# Proiect_TSC_v43.net
KiCad netlist of a schematic drawn in EAGLE
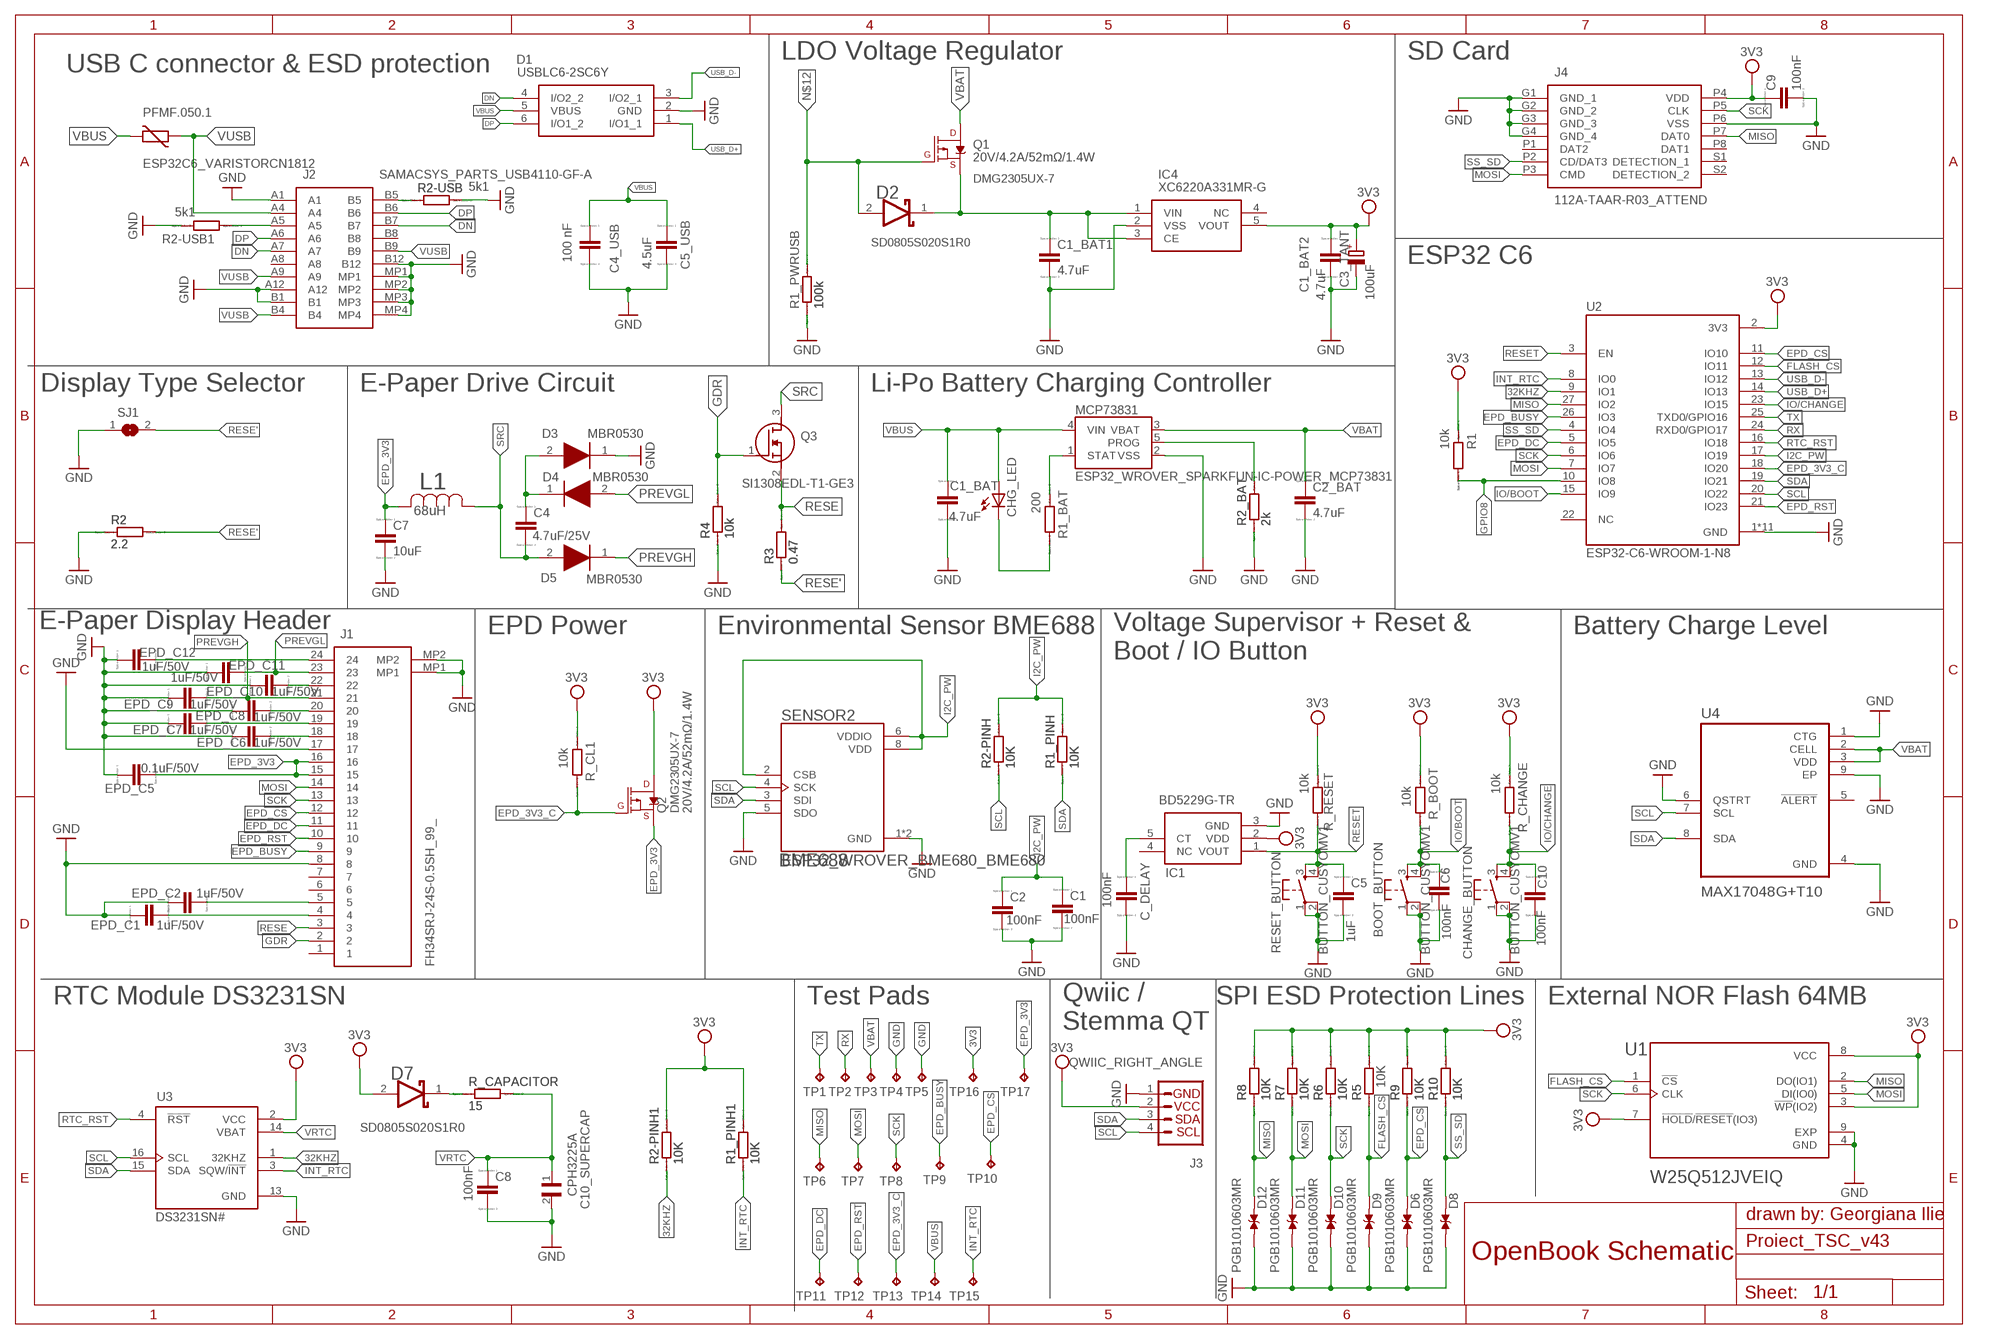
[diagram p0: schematic, sheet 1]

(export (version "E")
  (design (tool "Eeschema 10.0.6"))
  (components
    (comp (ref "BOOT_BUTTON")
      (value "BUTTON_CUSYOMV1")
      (footprint "eagle-import:MYBUTTON")
      (libsource (lib "eagle-import") (part "BUTTON_CUSYOMV1"))
    )
    (comp (ref "C1")
      (value "100nF")
      (footprint "eagle-import:EAGLE-LTSPICE_C0402")
      (libsource (lib "eagle-import") (part "EAGLE-LTSPICE_CC0402"))
    )
    (comp (ref "C1_BAT")
      (value "4.7uF")
      (footprint "eagle-import:EAGLE-LTSPICE_C0402")
      (libsource (lib "eagle-import") (part "EAGLE-LTSPICE_CC0402"))
    )
    (comp (ref "C1_BAT1")
      (value "4.7uF")
      (footprint "eagle-import:ESP32_WROVER_EAGLE-LTSPICE_C0402")
      (libsource (lib "eagle-import") (part "ESP32_WROVER_EAGLE-LTSPICE_CC0402"))
    )
    (comp (ref "C1_BAT2")
      (value "4.7uF")
      (footprint "eagle-import:ESP32_WROVER_EAGLE-LTSPICE_C0402")
      (libsource (lib "eagle-import") (part "ESP32_WROVER_EAGLE-LTSPICE_CC0402"))
    )
    (comp (ref "C2")
      (value "100nF")
      (footprint "eagle-import:EAGLE-LTSPICE_C0402")
      (libsource (lib "eagle-import") (part "EAGLE-LTSPICE_CC0402"))
    )
    (comp (ref "C2_BAT")
      (value "4.7uF")
      (footprint "eagle-import:EAGLE-LTSPICE_C0402")
      (libsource (lib "eagle-import") (part "EAGLE-LTSPICE_CC0402"))
    )
    (comp (ref "C3_TANT")
      (value "100uF")
      (footprint "eagle-import:RCL_CT3528")
      (libsource (lib "eagle-import") (part "RCL_CPOL-EUCT3528"))
    )
    (comp (ref "C4")
      (value "4.7uF/25V")
      (footprint "eagle-import:EAGLE-LTSPICE_C0402")
      (libsource (lib "eagle-import") (part "EAGLE-LTSPICE_CC0402"))
    )
    (comp (ref "C4_USB")
      (value "100 nF")
      (footprint "eagle-import:ESP32_WROVER_EAGLE-LTSPICE_C0402")
      (libsource (lib "eagle-import") (part "ESP32_WROVER_EAGLE-LTSPICE_CC0402"))
    )
    (comp (ref "C5")
      (value "1uF")
      (footprint "eagle-import:EAGLE-LTSPICE_C0402")
      (libsource (lib "eagle-import") (part "EAGLE-LTSPICE_CC0402"))
    )
    (comp (ref "C5_USB")
      (value "4.5uF")
      (footprint "eagle-import:ESP32_WROVER_EAGLE-LTSPICE_C0402")
      (libsource (lib "eagle-import") (part "ESP32_WROVER_EAGLE-LTSPICE_CC0402"))
    )
    (comp (ref "C6")
      (value "100nF")
      (footprint "eagle-import:EAGLE-LTSPICE_C0402")
      (libsource (lib "eagle-import") (part "EAGLE-LTSPICE_CC0402"))
    )
    (comp (ref "C7")
      (value "10uF")
      (footprint "eagle-import:EAGLE-LTSPICE_C0402")
      (libsource (lib "eagle-import") (part "EAGLE-LTSPICE_CC0402"))
    )
    (comp (ref "C8")
      (value "100nF")
      (footprint "eagle-import:EAGLE-LTSPICE_C0402")
      (libsource (lib "eagle-import") (part "EAGLE-LTSPICE_CC0402"))
    )
    (comp (ref "C9")
      (value "100nF")
      (footprint "eagle-import:EAGLE-LTSPICE_C0402")
      (libsource (lib "eagle-import") (part "EAGLE-LTSPICE_CC0402"))
    )
    (comp (ref "C10")
      (value "100nF")
      (footprint "eagle-import:EAGLE-LTSPICE_C0402")
      (libsource (lib "eagle-import") (part "EAGLE-LTSPICE_CC0402"))
    )
    (comp (ref "C10_SUPERCAP")
      (value "CPH3225A")
      (footprint "eagle-import:CAPCP3225X100N")
      (fields (field (name "MF") "Seiko Instruments"))
      (libsource (lib "eagle-import") (part "CPH3225A"))
    )
    (comp (ref "CHANGE_BUTTON")
      (value "BUTTON_CUSYOMV1")
      (footprint "eagle-import:MYBUTTON")
      (libsource (lib "eagle-import") (part "BUTTON_CUSYOMV1"))
    )
    (comp (ref "CHG_LED")
      (value "ADAFRUIT_LEDCHIP-LED0603")
      (footprint "eagle-import:ADAFRUIT_CHIP-LED0603")
      (libsource (lib "eagle-import") (part "ADAFRUIT_LEDCHIP-LED0603"))
    )
    (comp (ref "C_DELAY")
      (value "100nF")
      (footprint "eagle-import:EAGLE-LTSPICE_C0402")
      (libsource (lib "eagle-import") (part "EAGLE-LTSPICE_CC0402"))
    )
    (comp (ref "D1")
      (value "USBLC6-2SC6Y")
      (footprint "eagle-import:SOT95P280X145-6N")
      (fields (field (name "MF") "STMicroelectronics"))
      (libsource (lib "eagle-import") (part "USBLC6-2SC6Y"))
    )
    (comp (ref "D2")
      (value "ESP32_WROVER_AVX---SD0805S020S1R0_AVX_SD0805S020S1R0_0_0AVX_SD0805S020S1R0_0_0")
      (footprint "eagle-import:ESP32_WROVER_AVX---SD0805S020S1R0_AVX_SD0805S020S1R0_0")
      (fields
        (field (name "DIGIKEY_PART_NUMBER") "478-7800-1-ND")
        (field (name "MF") "AVX")
        (field (name "MOUSER_PART_NUMBER") "581-SD0805S020S1R0")
      )
      (libsource (lib "eagle-import") (part "ESP32_WROVER_AVX---SD0805S020S1R0_AVX_SD0805S020S1R0_0_0AVX_SD0805S020S1R0_0_0"))
    )
    (comp (ref "D3")
      (value "MBR0530")
      (footprint "eagle-import:SOD3716X135N")
      (fields (field (name "MF") "ON Semiconductor"))
      (libsource (lib "eagle-import") (part "MBR0530"))
    )
    (comp (ref "D4")
      (value "MBR0530")
      (footprint "eagle-import:SOD3716X135N")
      (fields (field (name "MF") "ON Semiconductor"))
      (libsource (lib "eagle-import") (part "MBR0530"))
    )
    (comp (ref "D5")
      (value "MBR0530")
      (footprint "eagle-import:SOD3716X135N")
      (fields (field (name "MF") "ON Semiconductor"))
      (libsource (lib "eagle-import") (part "MBR0530"))
    )
    (comp (ref "D6")
      (value "PGB1010603MR")
      (footprint "eagle-import:DIOC1608X36N")
      (fields (field (name "MF") "Littelfuse Inc."))
      (libsource (lib "eagle-import") (part "PGB1010603MR"))
    )
    (comp (ref "D7")
      (value "ESP32_WROVER_AVX---SD0805S020S1R0_AVX_SD0805S020S1R0_0_0AVX_SD0805S020S1R0_0_0")
      (footprint "eagle-import:ESP32_WROVER_AVX---SD0805S020S1R0_AVX_SD0805S020S1R0_0")
      (fields
        (field (name "DIGIKEY_PART_NUMBER") "478-7800-1-ND")
        (field (name "MF") "AVX")
        (field (name "MOUSER_PART_NUMBER") "581-SD0805S020S1R0")
      )
      (libsource (lib "eagle-import") (part "ESP32_WROVER_AVX---SD0805S020S1R0_AVX_SD0805S020S1R0_0_0AVX_SD0805S020S1R0_0_0"))
    )
    (comp (ref "D8")
      (value "PGB1010603MR")
      (footprint "eagle-import:DIOC1608X36N")
      (fields (field (name "MF") "Littelfuse Inc."))
      (libsource (lib "eagle-import") (part "PGB1010603MR"))
    )
    (comp (ref "D9")
      (value "PGB1010603MR")
      (footprint "eagle-import:DIOC1608X36N")
      (fields (field (name "MF") "Littelfuse Inc."))
      (libsource (lib "eagle-import") (part "PGB1010603MR"))
    )
    (comp (ref "D10")
      (value "PGB1010603MR")
      (footprint "eagle-import:DIOC1608X36N")
      (fields (field (name "MF") "Littelfuse Inc."))
      (libsource (lib "eagle-import") (part "PGB1010603MR"))
    )
    (comp (ref "D11")
      (value "PGB1010603MR")
      (footprint "eagle-import:DIOC1608X36N")
      (fields (field (name "MF") "Littelfuse Inc."))
      (libsource (lib "eagle-import") (part "PGB1010603MR"))
    )
    (comp (ref "D12")
      (value "PGB1010603MR")
      (footprint "eagle-import:DIOC1608X36N")
      (fields (field (name "MF") "Littelfuse Inc."))
      (libsource (lib "eagle-import") (part "PGB1010603MR"))
    )
    (comp (ref "EPD_C1")
      (value "1uF/50V")
      (footprint "eagle-import:EAGLE-LTSPICE_C0402")
      (libsource (lib "eagle-import") (part "EAGLE-LTSPICE_CC0402"))
    )
    (comp (ref "EPD_C2")
      (value "1uF/50V")
      (footprint "eagle-import:EAGLE-LTSPICE_C0402")
      (libsource (lib "eagle-import") (part "EAGLE-LTSPICE_CC0402"))
    )
    (comp (ref "EPD_C5")
      (value "0.1uF/50V")
      (footprint "eagle-import:EAGLE-LTSPICE_C0402")
      (libsource (lib "eagle-import") (part "EAGLE-LTSPICE_CC0402"))
    )
    (comp (ref "EPD_C6")
      (value "1uF/50V")
      (footprint "eagle-import:EAGLE-LTSPICE_C0402")
      (libsource (lib "eagle-import") (part "EAGLE-LTSPICE_CC0402"))
    )
    (comp (ref "EPD_C7")
      (value "1uF/50V")
      (footprint "eagle-import:EAGLE-LTSPICE_C0402")
      (libsource (lib "eagle-import") (part "EAGLE-LTSPICE_CC0402"))
    )
    (comp (ref "EPD_C8")
      (value "1uF/50V")
      (footprint "eagle-import:EAGLE-LTSPICE_C0402")
      (libsource (lib "eagle-import") (part "EAGLE-LTSPICE_CC0402"))
    )
    (comp (ref "EPD_C9")
      (value "1uF/50V")
      (footprint "eagle-import:EAGLE-LTSPICE_C0402")
      (libsource (lib "eagle-import") (part "EAGLE-LTSPICE_CC0402"))
    )
    (comp (ref "EPD_C10")
      (value "1uF/50V")
      (footprint "eagle-import:EAGLE-LTSPICE_C0402")
      (libsource (lib "eagle-import") (part "EAGLE-LTSPICE_CC0402"))
    )
    (comp (ref "EPD_C11")
      (value "1uF/50V")
      (footprint "eagle-import:EAGLE-LTSPICE_C0402")
      (libsource (lib "eagle-import") (part "EAGLE-LTSPICE_CC0402"))
    )
    (comp (ref "EPD_C12")
      (value "1uF/50V")
      (footprint "eagle-import:EAGLE-LTSPICE_C0402")
      (libsource (lib "eagle-import") (part "EAGLE-LTSPICE_CC0402"))
    )
    (comp (ref "IC1")
      (value "BD5229G-TR")
      (footprint "eagle-import:SOT95P280X125-5N")
      (fields (field (name "MOUSER_PART_NUMBER") "755-BD5229G-TR"))
      (libsource (lib "eagle-import") (part "BD5229G-TR"))
    )
    (comp (ref "IC4")
      (value "XC6220A331MR-G")
      (footprint "eagle-import:SOT95P280X120-5N")
      (fields (field (name "MOUSER_PART_NUMBER") "865-XC6220A331MR-G"))
      (libsource (lib "eagle-import") (part "XC6220A331MR-G"))
    )
    (comp (ref "J1")
      (value "FH34SRJ-24S-0.5SH_99_")
      (footprint "eagle-import:FH34SRJ24S05SH99")
      (fields
        (field (name "MANUFACTURER_PART_NUMBER") "FH34SRJ-24S-0.5SH(99)")
        (field (name "MOUSER_PART_NUMBER") "798-FH34SRJ24S05SH99")
      )
      (libsource (lib "eagle-import") (part "FH34SRJ-24S-0.5SH_99_"))
    )
    (comp (ref "J2")
      (value "SAMACSYS_PARTS_USB4110-GF-A")
      (footprint "eagle-import:SAMACSYS_PARTS_USB4110GFA")
      (fields
        (field (name "MANUFACTURER_PART_NUMBER") "USB4110-GF-A")
        (field (name "MOUSER_PART_NUMBER") "640-USB4110-GF-A")
      )
      (libsource (lib "eagle-import") (part "SAMACSYS_PARTS_USB4110-GF-A"))
    )
    (comp (ref "J3")
      (value "QWIIC_RIGHT_ANGLE")
      (footprint "eagle-import:JST04_1MM_RA")
      (libsource (lib "eagle-import") (part "QWIIC_CONNECTORJS-1MM"))
    )
    (comp (ref "J4")
      (value "112A-TAAR-R03_ATTEND")
      (footprint "eagle-import:112ATAARR03ATTEND")
      (fields (field (name "MANUFACTURER_PART_NUMBER") "112A-TAAR-R03 ATTEND"))
      (libsource (lib "eagle-import") (part "112A-TAAR-R03_ATTEND"))
    )
    (comp (ref "L1")
      (value "68uH")
      (footprint "eagle-import:IND_4828-WE-TPC_WRE")
      (fields
        (field (name "MANUFACTURER_PART_NUMBER") "744043680")
        (field (name "COPYRIGHT") "Copyright (C) 2024 Ultra Librarian. All rights reserved.")
      )
      (libsource (lib "eagle-import") (part "744043680IND_4828-WE-TPC_WRE"))
    )
    (comp (ref "MCP73831")
      (value "ESP32_WROVER_SPARKFUN-IC-POWER_MCP73831")
      (footprint "eagle-import:ESP32_WROVER_SPARKFUN-IC-POWER_SOT23-5")
      (libsource (lib "eagle-import") (part "ESP32_WROVER_SPARKFUN-IC-POWER_MCP73831"))
    )
    (comp (ref "PFMF.050.1")
      (value "ESP32C6_VARISTORCN1812")
      (footprint "eagle-import:ESP32C6_VARISTOR_CT_CN1812")
      (libsource (lib "eagle-import") (part "ESP32C6_VARISTORCN1812"))
    )
    (comp (ref "Q1")
      (value "20V/4.2A/52mΩ/1.4W")
      (footprint "eagle-import:ESP32_WROVER_SPARKFUN-DISCRETESEMI_SOT23-3")
      (libsource (lib "eagle-import") (part "ESP32_WROVER_SPARKFUN-DISCRETESEMI_MOSFET_PCH-DMG2305UX-7"))
    )
    (comp (ref "Q2")
      (value "20V/4.2A/52mΩ/1.4W")
      (footprint "eagle-import:ESP32_WROVER_SPARKFUN-DISCRETESEMI_SOT23-3")
      (libsource (lib "eagle-import") (part "ESP32_WROVER_SPARKFUN-DISCRETESEMI_MOSFET_PCH-DMG2305UX-7"))
    )
    (comp (ref "Q3")
      (value "SI1308EDL-T1-GE3")
      (footprint "eagle-import:SOT65P210X110-3N")
      (fields (field (name "MF") "Vishay Siliconix"))
      (libsource (lib "eagle-import") (part "SI1308EDL-T1-GE3"))
    )
    (comp (ref "R1")
      (value "10k")
      (footprint "eagle-import:ESP32_WROVER_EAGLE-LTSPICE_R0402")
      (libsource (lib "eagle-import") (part "ESP32_WROVER_EAGLE-LTSPICE_RR0402"))
    )
    (comp (ref "R1_BAT")
      (value "200")
      (footprint "eagle-import:ESP32_WROVER_EAGLE-LTSPICE_R0402")
      (libsource (lib "eagle-import") (part "ESP32_WROVER_EAGLE-LTSPICE_RR0402"))
    )
    (comp (ref "R1_PINH")
      (value "10K")
      (footprint "eagle-import:ESP32_WROVER_EAGLE-LTSPICE_R0402")
      (libsource (lib "eagle-import") (part "ESP32_WROVER_EAGLE-LTSPICE_RR0402"))
    )
    (comp (ref "R1_PINH1")
      (value "10K")
      (footprint "eagle-import:ESP32_WROVER_EAGLE-LTSPICE_R0402")
      (libsource (lib "eagle-import") (part "ESP32_WROVER_EAGLE-LTSPICE_RR0402"))
    )
    (comp (ref "R1_PWRUSB")
      (value "100k")
      (footprint "eagle-import:ESP32_WROVER_EAGLE-LTSPICE_R0402")
      (libsource (lib "eagle-import") (part "ESP32_WROVER_EAGLE-LTSPICE_RR0402"))
    )
    (comp (ref "R2")
      (value "2.2")
      (footprint "eagle-import:ESP32_WROVER_EAGLE-LTSPICE_R0402")
      (libsource (lib "eagle-import") (part "ESP32_WROVER_EAGLE-LTSPICE_RR0402"))
    )
    (comp (ref "R2-PINH")
      (value "10K")
      (footprint "eagle-import:ESP32_WROVER_EAGLE-LTSPICE_R0402")
      (libsource (lib "eagle-import") (part "ESP32_WROVER_EAGLE-LTSPICE_RR0402"))
    )
    (comp (ref "R2-PINH1")
      (value "10K")
      (footprint "eagle-import:ESP32_WROVER_EAGLE-LTSPICE_R0402")
      (libsource (lib "eagle-import") (part "ESP32_WROVER_EAGLE-LTSPICE_RR0402"))
    )
    (comp (ref "R2-USB")
      (value "5k1")
      (footprint "eagle-import:ESP32_WROVER_EAGLE-LTSPICE_R0402")
      (libsource (lib "eagle-import") (part "ESP32_WROVER_EAGLE-LTSPICE_RR0402"))
    )
    (comp (ref "R2-USB1")
      (value "5k1")
      (footprint "eagle-import:ESP32_WROVER_EAGLE-LTSPICE_R0402")
      (libsource (lib "eagle-import") (part "ESP32_WROVER_EAGLE-LTSPICE_RR0402"))
    )
    (comp (ref "R2_BAT")
      (value "2k")
      (footprint "eagle-import:ESP32_WROVER_EAGLE-LTSPICE_R0402")
      (libsource (lib "eagle-import") (part "ESP32_WROVER_EAGLE-LTSPICE_RR0402"))
    )
    (comp (ref "R3")
      (value "0.47")
      (footprint "eagle-import:ESP32_WROVER_EAGLE-LTSPICE_R0402")
      (libsource (lib "eagle-import") (part "ESP32_WROVER_EAGLE-LTSPICE_RR0402"))
    )
    (comp (ref "R4")
      (value "10k")
      (footprint "eagle-import:ESP32_WROVER_EAGLE-LTSPICE_R0402")
      (libsource (lib "eagle-import") (part "ESP32_WROVER_EAGLE-LTSPICE_RR0402"))
    )
    (comp (ref "R5")
      (value "10K")
      (footprint "eagle-import:ESP32_WROVER_EAGLE-LTSPICE_R0402")
      (libsource (lib "eagle-import") (part "ESP32_WROVER_EAGLE-LTSPICE_RR0402"))
    )
    (comp (ref "R6")
      (value "10K")
      (footprint "eagle-import:ESP32_WROVER_EAGLE-LTSPICE_R0402")
      (libsource (lib "eagle-import") (part "ESP32_WROVER_EAGLE-LTSPICE_RR0402"))
    )
    (comp (ref "R7")
      (value "10K")
      (footprint "eagle-import:ESP32_WROVER_EAGLE-LTSPICE_R0402")
      (libsource (lib "eagle-import") (part "ESP32_WROVER_EAGLE-LTSPICE_RR0402"))
    )
    (comp (ref "R8")
      (value "10K")
      (footprint "eagle-import:ESP32_WROVER_EAGLE-LTSPICE_R0402")
      (libsource (lib "eagle-import") (part "ESP32_WROVER_EAGLE-LTSPICE_RR0402"))
    )
    (comp (ref "R9")
      (value "10K")
      (footprint "eagle-import:ESP32_WROVER_EAGLE-LTSPICE_R0402")
      (libsource (lib "eagle-import") (part "ESP32_WROVER_EAGLE-LTSPICE_RR0402"))
    )
    (comp (ref "R10")
      (value "10K")
      (footprint "eagle-import:ESP32_WROVER_EAGLE-LTSPICE_R0402")
      (libsource (lib "eagle-import") (part "ESP32_WROVER_EAGLE-LTSPICE_RR0402"))
    )
    (comp (ref "RESET_BUTTON")
      (value "BUTTON_CUSYOMV1")
      (footprint "eagle-import:MYBUTTON")
      (libsource (lib "eagle-import") (part "BUTTON_CUSYOMV1"))
    )
    (comp (ref "R_BOOT")
      (value "10k")
      (footprint "eagle-import:ESP32_WROVER_EAGLE-LTSPICE_R0402")
      (libsource (lib "eagle-import") (part "ESP32_WROVER_EAGLE-LTSPICE_RR0402"))
    )
    (comp (ref "R_CAPACITOR")
      (value "15")
      (footprint "eagle-import:ESP32_WROVER_EAGLE-LTSPICE_R0402")
      (libsource (lib "eagle-import") (part "ESP32_WROVER_EAGLE-LTSPICE_RR0402"))
    )
    (comp (ref "R_CHANGE")
      (value "10k")
      (footprint "eagle-import:ESP32_WROVER_EAGLE-LTSPICE_R0402")
      (libsource (lib "eagle-import") (part "ESP32_WROVER_EAGLE-LTSPICE_RR0402"))
    )
    (comp (ref "R_CL1")
      (value "10k")
      (footprint "eagle-import:ESP32_WROVER_EAGLE-LTSPICE_R0402")
      (libsource (lib "eagle-import") (part "ESP32_WROVER_EAGLE-LTSPICE_RR0402"))
    )
    (comp (ref "R_RESET")
      (value "10k")
      (footprint "eagle-import:ESP32_WROVER_EAGLE-LTSPICE_R0402")
      (libsource (lib "eagle-import") (part "ESP32_WROVER_EAGLE-LTSPICE_RR0402"))
    )
    (comp (ref "SENSOR2")
      (value "ESP32_WROVER_BME680_BME680")
      (footprint "eagle-import:ESP32_WROVER_BME680_PSON80P300X300X100-8N")
      (fields (field (name "MF") "Bosch Sensortec") (field (name "MP") "BME680"))
      (libsource (lib "eagle-import") (part "ESP32_WROVER_BME680_BME680"))
    )
    (comp (ref "SJ1") (value "SJ") (footprint "eagle-import:SJ") (libsource (lib "eagle-import") (part "SJ")))
    (comp (ref "TP1")
      (value "TPTP20R")
      (footprint "eagle-import:TP20R")
      (libsource (lib "eagle-import") (part "TPTP20R"))
    )
    (comp (ref "TP2")
      (value "TPTP20R")
      (footprint "eagle-import:TP20R")
      (libsource (lib "eagle-import") (part "TPTP20R"))
    )
    (comp (ref "TP3")
      (value "TPTP20R")
      (footprint "eagle-import:TP20R")
      (libsource (lib "eagle-import") (part "TPTP20R"))
    )
    (comp (ref "TP4")
      (value "TPTP20R")
      (footprint "eagle-import:TP20R")
      (libsource (lib "eagle-import") (part "TPTP20R"))
    )
    (comp (ref "TP5")
      (value "TPTP20R")
      (footprint "eagle-import:TP20R")
      (libsource (lib "eagle-import") (part "TPTP20R"))
    )
    (comp (ref "TP6")
      (value "TPTP20R")
      (footprint "eagle-import:TP20R")
      (libsource (lib "eagle-import") (part "TPTP20R"))
    )
    (comp (ref "TP7")
      (value "TPTP20R")
      (footprint "eagle-import:TP20R")
      (libsource (lib "eagle-import") (part "TPTP20R"))
    )
    (comp (ref "TP8")
      (value "TPTP20R")
      (footprint "eagle-import:TP20R")
      (libsource (lib "eagle-import") (part "TPTP20R"))
    )
    (comp (ref "TP9")
      (value "TPTP20R")
      (footprint "eagle-import:TP20R")
      (libsource (lib "eagle-import") (part "TPTP20R"))
    )
    (comp (ref "TP10")
      (value "TPTP20R")
      (footprint "eagle-import:TP20R")
      (libsource (lib "eagle-import") (part "TPTP20R"))
    )
    (comp (ref "TP11")
      (value "TPTP20R")
      (footprint "eagle-import:TP20R")
      (libsource (lib "eagle-import") (part "TPTP20R"))
    )
    (comp (ref "TP12")
      (value "TPTP20R")
      (footprint "eagle-import:TP20R")
      (libsource (lib "eagle-import") (part "TPTP20R"))
    )
    (comp (ref "TP13")
      (value "TPTP20R")
      (footprint "eagle-import:TP20R")
      (libsource (lib "eagle-import") (part "TPTP20R"))
    )
    (comp (ref "TP14")
      (value "TPTP20R")
      (footprint "eagle-import:TP20R")
      (libsource (lib "eagle-import") (part "TPTP20R"))
    )
    (comp (ref "TP15")
      (value "TPTP20R")
      (footprint "eagle-import:TP20R")
      (libsource (lib "eagle-import") (part "TPTP20R"))
    )
    (comp (ref "TP16")
      (value "TPTP20R")
      (footprint "eagle-import:TP20R")
      (libsource (lib "eagle-import") (part "TPTP20R"))
    )
    (comp (ref "TP17")
      (value "TPTP20R")
      (footprint "eagle-import:TP20R")
      (libsource (lib "eagle-import") (part "TPTP20R"))
    )
    (comp (ref "U1")
      (value "W25Q512JVEIQ")
      (footprint "eagle-import:SON127P600X800X80-9N")
      (fields (field (name "MF") "Winbond Electronics"))
      (libsource (lib "eagle-import") (part "W25Q512JVEIQ"))
    )
    (comp (ref "U2")
      (value "ESP32-C6-WROOM-1-N8")
      (footprint "eagle-import:XCVR_ESP32-C6-WROOM-1-N8")
      (fields (field (name "MF") "Espressif Systems"))
      (libsource (lib "eagle-import") (part "ESP32-C6-WROOM-1-N8"))
    )
    (comp (ref "U3")
      (value "DS3231SN#")
      (footprint "eagle-import:SOIC127P1032X265-16N")
      (fields (field (name "MF") "Analog Devices"))
      (libsource (lib "eagle-import") (part "DS3231SN#"))
    )
    (comp (ref "U4")
      (value "MAX17048G+T10")
      (footprint "eagle-import:SON50P200X200X80-9N")
      (fields (field (name "MF") "Analog Devices"))
      (libsource (lib "eagle-import") (part "MAX17048G+T10"))
    )
  )
  (nets
    (net (code "1") (name "3V3") (class "Default")
      (node (ref "C1_BAT2") (pin "1") (pinfunction "1_1") (pintype "passive"))
      (node (ref "C3_TANT") (pin "+") (pinfunction "+_+") (pintype "passive"))
      (node (ref "C9") (pin "1") (pinfunction "1_1") (pintype "passive"))
      (node (ref "D7") (pin "2") (pinfunction "ANODE_2") (pintype "bidirectional"))
      (node (ref "IC1") (pin "2") (pinfunction "VDD_2") (pintype "bidirectional"))
      (node (ref "IC4") (pin "5") (pinfunction "VOUT_5") (pintype "bidirectional"))
      (node (ref "J3") (pin "2") (pinfunction "2_2") (pintype "power_in"))
      (node (ref "J4") (pin "P4") (pinfunction "VDD_P4") (pintype "bidirectional"))
      (node (ref "Q2") (pin "3") (pinfunction "D_3") (pintype "bidirectional"))
      (node (ref "R1") (pin "2") (pinfunction "2_2") (pintype "passive"))
      (node (ref "R10") (pin "2") (pinfunction "2_2") (pintype "passive"))
      (node (ref "R1_PINH1") (pin "2") (pinfunction "2_2") (pintype "passive"))
      (node (ref "R2-PINH1") (pin "2") (pinfunction "2_2") (pintype "passive"))
      (node (ref "R5") (pin "2") (pinfunction "2_2") (pintype "passive"))
      (node (ref "R6") (pin "2") (pinfunction "2_2") (pintype "passive"))
      (node (ref "R7") (pin "2") (pinfunction "2_2") (pintype "passive"))
      (node (ref "R8") (pin "2") (pinfunction "2_2") (pintype "passive"))
      (node (ref "R9") (pin "2") (pinfunction "2_2") (pintype "passive"))
      (node (ref "R_BOOT") (pin "2") (pinfunction "2_2") (pintype "passive"))
      (node (ref "R_CHANGE") (pin "2") (pinfunction "2_2") (pintype "passive"))
      (node (ref "R_CL1") (pin "2") (pinfunction "2_2") (pintype "passive"))
      (node (ref "R_RESET") (pin "2") (pinfunction "2_2") (pintype "passive"))
      (node (ref "TP16") (pin "TP") (pinfunction "TP_TP") (pintype "input"))
      (node (ref "U1") (pin "3") (pinfunction "~{WP}(IO2)_3") (pintype "bidirectional"))
      (node (ref "U1") (pin "7") (pinfunction "~{HOLD}/~{RESET}(IO3)_7") (pintype "bidirectional"))
      (node (ref "U1") (pin "8") (pinfunction "VCC_8") (pintype "power_in"))
      (node (ref "U2") (pin "2") (pinfunction "3V3_2") (pintype "power_in"))
      (node (ref "U3") (pin "2") (pinfunction "VCC_2") (pintype "power_in"))
    )
    (net (code "2") (name "32KHZ") (class "Default")
      (node (ref "R2-PINH1") (pin "1") (pinfunction "1_1") (pintype "passive"))
      (node (ref "U2") (pin "9") (pinfunction "IO1_9") (pintype "bidirectional"))
      (node (ref "U3") (pin "1") (pinfunction "32KHZ_1") (pintype "output"))
    )
    (net (code "3") (name "DN") (class "Default")
      (node (ref "D1") (pin "4") (pinfunction "I/O2_2_4") (pintype "bidirectional"))
      (node (ref "J2") (pin "A7") (pinfunction "A7_A7") (pintype "bidirectional"))
      (node (ref "J2") (pin "B7") (pinfunction "B7_B7") (pintype "bidirectional"))
    )
    (net (code "4") (name "DP") (class "Default")
      (node (ref "D1") (pin "6") (pinfunction "I/O1_2_6") (pintype "bidirectional"))
      (node (ref "J2") (pin "A6") (pinfunction "A6_A6") (pintype "bidirectional"))
      (node (ref "J2") (pin "B6") (pinfunction "B6_B6") (pintype "bidirectional"))
    )
    (net (code "5") (name "EPD_3V3") (class "Default")
      (node (ref "C7") (pin "1") (pinfunction "1_1") (pintype "passive"))
      (node (ref "EPD_C5") (pin "2") (pinfunction "2_2") (pintype "passive"))
      (node (ref "J1") (pin "15") (pinfunction "15_15") (pintype "bidirectional"))
      (node (ref "J1") (pin "16") (pinfunction "16_16") (pintype "bidirectional"))
      (node (ref "L1") (pin "2") (pinfunction "2_2") (pintype "passive"))
      (node (ref "Q2") (pin "2") (pinfunction "S_2") (pintype "bidirectional"))
      (node (ref "TP17") (pin "TP") (pinfunction "TP_TP") (pintype "input"))
    )
    (net (code "6") (name "EPD_3V3_C") (class "Default")
      (node (ref "Q2") (pin "1") (pinfunction "G_1") (pintype "bidirectional"))
      (node (ref "R_CL1") (pin "1") (pinfunction "1_1") (pintype "passive"))
      (node (ref "TP13") (pin "TP") (pinfunction "TP_TP") (pintype "input"))
      (node (ref "U2") (pin "18") (pinfunction "IO20_18") (pintype "bidirectional"))
    )
    (net (code "7") (name "EPD_BUSY") (class "Default")
      (node (ref "J1") (pin "9") (pinfunction "9_9") (pintype "bidirectional"))
      (node (ref "TP9") (pin "TP") (pinfunction "TP_TP") (pintype "input"))
      (node (ref "U2") (pin "26") (pinfunction "IO3_26") (pintype "bidirectional"))
    )
    (net (code "8") (name "EPD_CS") (class "Default")
      (node (ref "D6") (pin "2") (pinfunction "2_2") (pintype "passive"))
      (node (ref "J1") (pin "12") (pinfunction "12_12") (pintype "bidirectional"))
      (node (ref "R9") (pin "1") (pinfunction "1_1") (pintype "passive"))
      (node (ref "TP10") (pin "TP") (pinfunction "TP_TP") (pintype "input"))
      (node (ref "U2") (pin "11") (pinfunction "IO10_11") (pintype "bidirectional"))
    )
    (net (code "9") (name "EPD_DC") (class "Default")
      (node (ref "J1") (pin "11") (pinfunction "11_11") (pintype "bidirectional"))
      (node (ref "TP11") (pin "TP") (pinfunction "TP_TP") (pintype "input"))
      (node (ref "U2") (pin "5") (pinfunction "IO5_5") (pintype "bidirectional"))
    )
    (net (code "10") (name "EPD_RST") (class "Default")
      (node (ref "J1") (pin "10") (pinfunction "10_10") (pintype "bidirectional"))
      (node (ref "TP12") (pin "TP") (pinfunction "TP_TP") (pintype "input"))
      (node (ref "U2") (pin "21") (pinfunction "IO23_21") (pintype "bidirectional"))
    )
    (net (code "11") (name "FLASH_CS") (class "Default")
      (node (ref "D9") (pin "2") (pinfunction "2_2") (pintype "passive"))
      (node (ref "R5") (pin "1") (pinfunction "1_1") (pintype "passive"))
      (node (ref "U1") (pin "1") (pinfunction "~{CS}_1") (pintype "input"))
      (node (ref "U2") (pin "12") (pinfunction "IO11_12") (pintype "bidirectional"))
    )
    (net (code "12") (name "GDR") (class "Default")
      (node (ref "J1") (pin "2") (pinfunction "2_2") (pintype "bidirectional"))
      (node (ref "Q3") (pin "1") (pinfunction "G_1") (pintype "bidirectional"))
      (node (ref "R4") (pin "2") (pinfunction "2_2") (pintype "passive"))
    )
    (net (code "13") (name "GND") (class "Default")
      (node (ref "BOOT_BUTTON") (pin "1") (pinfunction "1_1") (pintype "passive"))
      (node (ref "BOOT_BUTTON") (pin "2") (pinfunction "2_2") (pintype "passive"))
      (node (ref "C1") (pin "2") (pinfunction "2_2") (pintype "passive"))
      (node (ref "C10") (pin "2") (pinfunction "2_2") (pintype "passive"))
      (node (ref "C10_SUPERCAP") (pin "2") (pinfunction "2_2") (pintype "passive"))
      (node (ref "C1_BAT") (pin "2") (pinfunction "2_2") (pintype "passive"))
      (node (ref "C1_BAT1") (pin "2") (pinfunction "2_2") (pintype "passive"))
      (node (ref "C1_BAT2") (pin "2") (pinfunction "2_2") (pintype "passive"))
      (node (ref "C2") (pin "2") (pinfunction "2_2") (pintype "passive"))
      (node (ref "C2_BAT") (pin "2") (pinfunction "2_2") (pintype "passive"))
      (node (ref "C3_TANT") (pin "-") (pinfunction "-_-") (pintype "passive"))
      (node (ref "C4_USB") (pin "2") (pinfunction "2_2") (pintype "passive"))
      (node (ref "C5") (pin "2") (pinfunction "2_2") (pintype "passive"))
      (node (ref "C5_USB") (pin "2") (pinfunction "2_2") (pintype "passive"))
      (node (ref "C6") (pin "2") (pinfunction "2_2") (pintype "passive"))
      (node (ref "C7") (pin "2") (pinfunction "2_2") (pintype "passive"))
      (node (ref "C8") (pin "2") (pinfunction "2_2") (pintype "passive"))
      (node (ref "C9") (pin "2") (pinfunction "2_2") (pintype "passive"))
      (node (ref "CHANGE_BUTTON") (pin "1") (pinfunction "1_1") (pintype "passive"))
      (node (ref "CHANGE_BUTTON") (pin "2") (pinfunction "2_2") (pintype "passive"))
      (node (ref "C_DELAY") (pin "2") (pinfunction "2_2") (pintype "passive"))
      (node (ref "D1") (pin "2") (pinfunction "GND_2") (pintype "bidirectional"))
      (node (ref "D10") (pin "1") (pinfunction "1_1") (pintype "passive"))
      (node (ref "D11") (pin "1") (pinfunction "1_1") (pintype "passive"))
      (node (ref "D12") (pin "1") (pinfunction "1_1") (pintype "passive"))
      (node (ref "D3") (pin "1") (pinfunction "K_1") (pintype "bidirectional"))
      (node (ref "D6") (pin "1") (pinfunction "1_1") (pintype "passive"))
      (node (ref "D8") (pin "1") (pinfunction "1_1") (pintype "passive"))
      (node (ref "D9") (pin "1") (pinfunction "1_1") (pintype "passive"))
      (node (ref "EPD_C1") (pin "1") (pinfunction "1_1") (pintype "passive"))
      (node (ref "EPD_C10") (pin "1") (pinfunction "1_1") (pintype "passive"))
      (node (ref "EPD_C11") (pin "1") (pinfunction "1_1") (pintype "passive"))
      (node (ref "EPD_C12") (pin "1") (pinfunction "1_1") (pintype "passive"))
      (node (ref "EPD_C2") (pin "1") (pinfunction "1_1") (pintype "passive"))
      (node (ref "EPD_C5") (pin "1") (pinfunction "1_1") (pintype "passive"))
      (node (ref "EPD_C6") (pin "1") (pinfunction "1_1") (pintype "passive"))
      (node (ref "EPD_C7") (pin "1") (pinfunction "1_1") (pintype "passive"))
      (node (ref "EPD_C8") (pin "1") (pinfunction "1_1") (pintype "passive"))
      (node (ref "EPD_C9") (pin "1") (pinfunction "1_1") (pintype "passive"))
      (node (ref "IC1") (pin "3") (pinfunction "GND_3") (pintype "bidirectional"))
      (node (ref "IC4") (pin "2") (pinfunction "VSS_2") (pintype "bidirectional"))
      (node (ref "J1") (pin "17") (pinfunction "17_17") (pintype "bidirectional"))
      (node (ref "J1") (pin "8") (pinfunction "8_8") (pintype "bidirectional"))
      (node (ref "J1") (pin "MP1") (pinfunction "MP1_MP1") (pintype "bidirectional"))
      (node (ref "J1") (pin "MP2") (pinfunction "MP2_MP2") (pintype "bidirectional"))
      (node (ref "J2") (pin "A1") (pinfunction "A1_A1") (pintype "bidirectional"))
      (node (ref "J2") (pin "A12") (pinfunction "A12_A12") (pintype "bidirectional"))
      (node (ref "J2") (pin "B1") (pinfunction "B1_B1") (pintype "bidirectional"))
      (node (ref "J2") (pin "B12") (pinfunction "B12_B12") (pintype "bidirectional"))
      (node (ref "J2") (pin "MP1") (pinfunction "MP1_MP1") (pintype "bidirectional"))
      (node (ref "J2") (pin "MP2") (pinfunction "MP2_MP2") (pintype "bidirectional"))
      (node (ref "J2") (pin "MP3") (pinfunction "MP3_MP3") (pintype "bidirectional"))
      (node (ref "J2") (pin "MP4") (pinfunction "MP4_MP4") (pintype "bidirectional"))
      (node (ref "J3") (pin "1") (pinfunction "1_1") (pintype "power_in"))
      (node (ref "J4") (pin "G1") (pinfunction "GND_1_G1") (pintype "bidirectional"))
      (node (ref "J4") (pin "G2") (pinfunction "GND_2_G2") (pintype "bidirectional"))
      (node (ref "J4") (pin "G3") (pinfunction "GND_3_G3") (pintype "bidirectional"))
      (node (ref "J4") (pin "G4") (pinfunction "GND_4_G4") (pintype "bidirectional"))
      (node (ref "J4") (pin "P6") (pinfunction "VSS_P6") (pintype "bidirectional"))
      (node (ref "MCP73831") (pin "2") (pinfunction "VSS_2") (pintype "power_in"))
      (node (ref "R1_PWRUSB") (pin "1") (pinfunction "1_1") (pintype "passive"))
      (node (ref "R2") (pin "1") (pinfunction "1_1") (pintype "passive"))
      (node (ref "R2-USB") (pin "2") (pinfunction "2_2") (pintype "passive"))
      (node (ref "R2-USB1") (pin "1") (pinfunction "1_1") (pintype "passive"))
      (node (ref "R2_BAT") (pin "1") (pinfunction "1_1") (pintype "passive"))
      (node (ref "R4") (pin "1") (pinfunction "1_1") (pintype "passive"))
      (node (ref "RESET_BUTTON") (pin "1") (pinfunction "1_1") (pintype "passive"))
      (node (ref "RESET_BUTTON") (pin "2") (pinfunction "2_2") (pintype "passive"))
      (node (ref "SENSOR2") (pin "1") (pinfunction "GND_1") (pintype "power_in"))
      (node (ref "SENSOR2") (pin "5") (pinfunction "SDO_5") (pintype "bidirectional"))
      (node (ref "SENSOR2") (pin "7") (pinfunction "GND_7") (pintype "power_in"))
      (node (ref "SJ1") (pin "1") (pinfunction "1_1") (pintype "passive"))
      (node (ref "TP4") (pin "TP") (pinfunction "TP_TP") (pintype "input"))
      (node (ref "TP5") (pin "TP") (pinfunction "TP_TP") (pintype "input"))
      (node (ref "U1") (pin "4") (pinfunction "GND_4") (pintype "power_in"))
      (node (ref "U1") (pin "9") (pinfunction "EXP_9") (pintype "passive"))
      (node (ref "U2") (pin "1") (pinfunction "GND_1") (pintype "power_in"))
      (node (ref "U2") (pin "28") (pinfunction "GND_28") (pintype "power_in"))
      (node (ref "U2") (pin "29_1") (pinfunction "GND_29_1") (pintype "power_in"))
      (node (ref "U2") (pin "29_2") (pinfunction "GND_29_2") (pintype "power_in"))
      (node (ref "U2") (pin "29_3") (pinfunction "GND_29_3") (pintype "power_in"))
      (node (ref "U2") (pin "29_4") (pinfunction "GND_29_4") (pintype "power_in"))
      (node (ref "U2") (pin "29_5") (pinfunction "GND_29_5") (pintype "power_in"))
      (node (ref "U2") (pin "29_6") (pinfunction "GND_29_6") (pintype "power_in"))
      (node (ref "U2") (pin "29_7") (pinfunction "GND_29_7") (pintype "power_in"))
      (node (ref "U2") (pin "29_8") (pinfunction "GND_29_8") (pintype "power_in"))
      (node (ref "U2") (pin "29_9") (pinfunction "GND_29_9") (pintype "power_in"))
      (node (ref "U3") (pin "13") (pinfunction "GND_13") (pintype "power_in"))
      (node (ref "U4") (pin "1") (pinfunction "CTG_1") (pintype "power_in"))
      (node (ref "U4") (pin "4") (pinfunction "GND_4") (pintype "power_in"))
      (node (ref "U4") (pin "6") (pinfunction "QSTRT_6") (pintype "input"))
      (node (ref "U4") (pin "9") (pinfunction "EP_9") (pintype "power_in"))
    )
    (net (code "14") (name "GPIO8") (class "Default")
      (node (ref "R1") (pin "1") (pinfunction "1_1") (pintype "passive"))
      (node (ref "U2") (pin "10") (pinfunction "IO8_10") (pintype "bidirectional"))
    )
    (net (code "15") (name "I2C_PW") (class "Default")
      (node (ref "C1") (pin "1") (pinfunction "1_1") (pintype "passive"))
      (node (ref "C2") (pin "1") (pinfunction "1_1") (pintype "passive"))
      (node (ref "R1_PINH") (pin "2") (pinfunction "2_2") (pintype "passive"))
      (node (ref "R2-PINH") (pin "2") (pinfunction "2_2") (pintype "passive"))
      (node (ref "SENSOR2") (pin "2") (pinfunction "CSB_2") (pintype "input"))
      (node (ref "SENSOR2") (pin "6") (pinfunction "VDDIO_6") (pintype "power_in"))
      (node (ref "SENSOR2") (pin "8") (pinfunction "VDD_8") (pintype "power_in"))
      (node (ref "U2") (pin "17") (pinfunction "IO19_17") (pintype "bidirectional"))
    )
    (net (code "16") (name "INT_RTC") (class "Default")
      (node (ref "R1_PINH1") (pin "1") (pinfunction "1_1") (pintype "passive"))
      (node (ref "TP15") (pin "TP") (pinfunction "TP_TP") (pintype "input"))
      (node (ref "U2") (pin "8") (pinfunction "IO0_8") (pintype "bidirectional"))
      (node (ref "U3") (pin "3") (pinfunction "SQW/~{INT}_3") (pintype "output"))
    )
    (net (code "17") (name "IO{slash}BOOT") (class "Default")
      (node (ref "BOOT_BUTTON") (pin "3") (pinfunction "3_3") (pintype "passive"))
      (node (ref "BOOT_BUTTON") (pin "4") (pinfunction "4_4") (pintype "passive"))
      (node (ref "C6") (pin "1") (pinfunction "1_1") (pintype "passive"))
      (node (ref "R_BOOT") (pin "1") (pinfunction "1_1") (pintype "passive"))
      (node (ref "U2") (pin "15") (pinfunction "IO9_15") (pintype "bidirectional"))
    )
    (net (code "18") (name "IO{slash}CHANGE") (class "Default")
      (node (ref "C10") (pin "1") (pinfunction "1_1") (pintype "passive"))
      (node (ref "CHANGE_BUTTON") (pin "3") (pinfunction "3_3") (pintype "passive"))
      (node (ref "CHANGE_BUTTON") (pin "4") (pinfunction "4_4") (pintype "passive"))
      (node (ref "R_CHANGE") (pin "1") (pinfunction "1_1") (pintype "passive"))
      (node (ref "U2") (pin "23") (pinfunction "IO15_23") (pintype "bidirectional"))
    )
    (net (code "19") (name "MISO") (class "Default")
      (node (ref "D12") (pin "2") (pinfunction "2_2") (pintype "passive"))
      (node (ref "J4") (pin "P7") (pinfunction "DAT0_P7") (pintype "bidirectional"))
      (node (ref "R8") (pin "1") (pinfunction "1_1") (pintype "passive"))
      (node (ref "TP6") (pin "TP") (pinfunction "TP_TP") (pintype "input"))
      (node (ref "U1") (pin "2") (pinfunction "DO(IO1)_2") (pintype "bidirectional"))
      (node (ref "U2") (pin "27") (pinfunction "IO2_27") (pintype "bidirectional"))
    )
    (net (code "20") (name "MOSI") (class "Default")
      (node (ref "D11") (pin "2") (pinfunction "2_2") (pintype "passive"))
      (node (ref "J1") (pin "14") (pinfunction "14_14") (pintype "bidirectional"))
      (node (ref "J4") (pin "P3") (pinfunction "CMD_P3") (pintype "bidirectional"))
      (node (ref "R7") (pin "1") (pinfunction "1_1") (pintype "passive"))
      (node (ref "TP7") (pin "TP") (pinfunction "TP_TP") (pintype "input"))
      (node (ref "U1") (pin "5") (pinfunction "DI(IO0)_5") (pintype "bidirectional"))
      (node (ref "U2") (pin "7") (pinfunction "IO7_7") (pintype "bidirectional"))
    )
    (net (code "21") (name "N$12") (class "Default")
      (node (ref "D2") (pin "2") (pinfunction "ANODE_2") (pintype "bidirectional"))
      (node (ref "Q1") (pin "1") (pinfunction "G_1") (pintype "bidirectional"))
      (node (ref "R1_PWRUSB") (pin "2") (pinfunction "2_2") (pintype "passive"))
    )
    (net (code "22") (name "Net-(CHG_LED-PadC)") (class "Default")
      (node (ref "CHG_LED") (pin "C") (pinfunction "C_C") (pintype "passive"))
      (node (ref "R1_BAT") (pin "1") (pinfunction "1_1") (pintype "passive"))
    )
    (net (code "23") (name "Net-(D2-CATHODE)") (class "Default")
      (node (ref "C1_BAT1") (pin "1") (pinfunction "1_1") (pintype "passive"))
      (node (ref "D2") (pin "1") (pinfunction "CATHODE_1") (pintype "bidirectional"))
      (node (ref "IC4") (pin "1") (pinfunction "VIN_1") (pintype "bidirectional"))
      (node (ref "IC4") (pin "3") (pinfunction "CE_3") (pintype "bidirectional"))
      (node (ref "Q1") (pin "2") (pinfunction "S_2") (pintype "bidirectional"))
    )
    (net (code "24") (name "Net-(D3-A)") (class "Default")
      (node (ref "C4") (pin "1") (pinfunction "1_1") (pintype "passive"))
      (node (ref "D3") (pin "2") (pinfunction "A_2") (pintype "bidirectional"))
      (node (ref "D4") (pin "1") (pinfunction "K_1") (pintype "bidirectional"))
    )
    (net (code "25") (name "Net-(D7-CATHODE)") (class "Default")
      (node (ref "D7") (pin "1") (pinfunction "CATHODE_1") (pintype "bidirectional"))
      (node (ref "R_CAPACITOR") (pin "1") (pinfunction "1_1") (pintype "passive"))
    )
    (net (code "26") (name "Net-(EPD_C1-Pad2)") (class "Default")
      (node (ref "EPD_C1") (pin "2") (pinfunction "2_2") (pintype "passive"))
      (node (ref "J1") (pin "4") (pinfunction "4_4") (pintype "bidirectional"))
    )
    (net (code "27") (name "Net-(EPD_C2-Pad2)") (class "Default")
      (node (ref "EPD_C2") (pin "2") (pinfunction "2_2") (pintype "passive"))
      (node (ref "J1") (pin "5") (pinfunction "5_5") (pintype "bidirectional"))
    )
    (net (code "28") (name "Net-(EPD_C6-Pad2)") (class "Default")
      (node (ref "EPD_C6") (pin "2") (pinfunction "2_2") (pintype "passive"))
      (node (ref "J1") (pin "18") (pinfunction "18_18") (pintype "bidirectional"))
    )
    (net (code "29") (name "Net-(EPD_C7-Pad2)") (class "Default")
      (node (ref "EPD_C7") (pin "2") (pinfunction "2_2") (pintype "passive"))
      (node (ref "J1") (pin "19") (pinfunction "19_19") (pintype "bidirectional"))
    )
    (net (code "30") (name "Net-(EPD_C8-Pad2)") (class "Default")
      (node (ref "EPD_C8") (pin "2") (pinfunction "2_2") (pintype "passive"))
      (node (ref "J1") (pin "20") (pinfunction "20_20") (pintype "bidirectional"))
    )
    (net (code "31") (name "Net-(EPD_C10-Pad2)") (class "Default")
      (node (ref "EPD_C10") (pin "2") (pinfunction "2_2") (pintype "passive"))
      (node (ref "J1") (pin "22") (pinfunction "22_22") (pintype "bidirectional"))
    )
    (net (code "32") (name "Net-(EPD_C12-Pad2)") (class "Default")
      (node (ref "EPD_C12") (pin "2") (pinfunction "2_2") (pintype "passive"))
      (node (ref "J1") (pin "24") (pinfunction "24_24") (pintype "bidirectional"))
    )
    (net (code "33") (name "Net-(IC1-CT)") (class "Default")
      (node (ref "C_DELAY") (pin "1") (pinfunction "1_1") (pintype "passive"))
      (node (ref "IC1") (pin "5") (pinfunction "CT_5") (pintype "bidirectional"))
    )
    (net (code "34") (name "Net-(J2-PadA5)") (class "Default")
      (node (ref "J2") (pin "A5") (pinfunction "A5_A5") (pintype "bidirectional"))
      (node (ref "R2-USB1") (pin "2") (pinfunction "2_2") (pintype "passive"))
    )
    (net (code "35") (name "Net-(J2-PadB5)") (class "Default")
      (node (ref "J2") (pin "B5") (pinfunction "B5_B5") (pintype "bidirectional"))
      (node (ref "R2-USB") (pin "1") (pinfunction "1_1") (pintype "passive"))
    )
    (net (code "36") (name "Net-(MCP73831-PROG)") (class "Default")
      (node (ref "MCP73831") (pin "5") (pinfunction "PROG_5") (pintype "input"))
      (node (ref "R2_BAT") (pin "2") (pinfunction "2_2") (pintype "passive"))
    )
    (net (code "37") (name "Net-(MCP73831-STAT)") (class "Default")
      (node (ref "MCP73831") (pin "1") (pinfunction "STAT_1") (pintype "output"))
      (node (ref "R1_BAT") (pin "2") (pinfunction "2_2") (pintype "passive"))
    )
    (net (code "38") (name "PREVGH") (class "Default")
      (node (ref "D5") (pin "1") (pinfunction "K_1") (pintype "bidirectional"))
      (node (ref "EPD_C9") (pin "2") (pinfunction "2_2") (pintype "passive"))
      (node (ref "J1") (pin "21") (pinfunction "21_21") (pintype "bidirectional"))
    )
    (net (code "39") (name "PREVGL") (class "Default")
      (node (ref "D4") (pin "2") (pinfunction "A_2") (pintype "bidirectional"))
      (node (ref "EPD_C11") (pin "2") (pinfunction "2_2") (pintype "passive"))
      (node (ref "J1") (pin "23") (pinfunction "23_23") (pintype "bidirectional"))
    )
    (net (code "40") (name "RESE") (class "Default")
      (node (ref "J1") (pin "3") (pinfunction "3_3") (pintype "bidirectional"))
      (node (ref "Q3") (pin "2") (pinfunction "S_2") (pintype "bidirectional"))
      (node (ref "R3") (pin "2") (pinfunction "2_2") (pintype "passive"))
    )
    (net (code "41") (name "RESE'") (class "Default")
      (node (ref "R2") (pin "2") (pinfunction "2_2") (pintype "passive"))
      (node (ref "R3") (pin "1") (pinfunction "1_1") (pintype "passive"))
      (node (ref "SJ1") (pin "2") (pinfunction "2_2") (pintype "passive"))
    )
    (net (code "42") (name "RESET") (class "Default")
      (node (ref "C5") (pin "1") (pinfunction "1_1") (pintype "passive"))
      (node (ref "IC1") (pin "1") (pinfunction "VOUT_1") (pintype "bidirectional"))
      (node (ref "RESET_BUTTON") (pin "3") (pinfunction "3_3") (pintype "passive"))
      (node (ref "RESET_BUTTON") (pin "4") (pinfunction "4_4") (pintype "passive"))
      (node (ref "R_RESET") (pin "1") (pinfunction "1_1") (pintype "passive"))
      (node (ref "U2") (pin "3") (pinfunction "EN_3") (pintype "input"))
    )
    (net (code "43") (name "RTC_RST") (class "Default")
      (node (ref "U2") (pin "16") (pinfunction "IO18_16") (pintype "bidirectional"))
      (node (ref "U3") (pin "4") (pinfunction "~{RST}_4") (pintype "input"))
    )
    (net (code "44") (name "RX") (class "Default")
      (node (ref "TP2") (pin "TP") (pinfunction "TP_TP") (pintype "input"))
      (node (ref "U2") (pin "24") (pinfunction "RXD0/GPIO17_24") (pintype "bidirectional"))
    )
    (net (code "45") (name "SCK") (class "Default")
      (node (ref "D10") (pin "2") (pinfunction "2_2") (pintype "passive"))
      (node (ref "J1") (pin "13") (pinfunction "13_13") (pintype "bidirectional"))
      (node (ref "J4") (pin "P5") (pinfunction "CLK_P5") (pintype "bidirectional"))
      (node (ref "R6") (pin "1") (pinfunction "1_1") (pintype "passive"))
      (node (ref "TP8") (pin "TP") (pinfunction "TP_TP") (pintype "input"))
      (node (ref "U1") (pin "6") (pinfunction "CLK_6") (pintype "input"))
      (node (ref "U2") (pin "6") (pinfunction "IO6_6") (pintype "bidirectional"))
    )
    (net (code "46") (name "SCL") (class "Default")
      (node (ref "J3") (pin "4") (pinfunction "4_4") (pintype "passive"))
      (node (ref "R2-PINH") (pin "1") (pinfunction "1_1") (pintype "passive"))
      (node (ref "SENSOR2") (pin "4") (pinfunction "SCK_4") (pintype "input"))
      (node (ref "U2") (pin "20") (pinfunction "IO22_20") (pintype "bidirectional"))
      (node (ref "U3") (pin "16") (pinfunction "SCL_16") (pintype "input"))
      (node (ref "U4") (pin "7") (pinfunction "SCL_7") (pintype "input"))
    )
    (net (code "47") (name "SDA") (class "Default")
      (node (ref "J3") (pin "3") (pinfunction "3_3") (pintype "passive"))
      (node (ref "R1_PINH") (pin "1") (pinfunction "1_1") (pintype "passive"))
      (node (ref "SENSOR2") (pin "3") (pinfunction "SDI_3") (pintype "bidirectional"))
      (node (ref "U2") (pin "19") (pinfunction "IO21_19") (pintype "bidirectional"))
      (node (ref "U3") (pin "15") (pinfunction "SDA_15") (pintype "bidirectional"))
      (node (ref "U4") (pin "8") (pinfunction "SDA_8") (pintype "bidirectional"))
    )
    (net (code "48") (name "SRC") (class "Default")
      (node (ref "C4") (pin "2") (pinfunction "2_2") (pintype "passive"))
      (node (ref "D5") (pin "2") (pinfunction "A_2") (pintype "bidirectional"))
      (node (ref "L1") (pin "1") (pinfunction "1_1") (pintype "passive"))
      (node (ref "Q3") (pin "3") (pinfunction "D_3") (pintype "bidirectional"))
    )
    (net (code "49") (name "SS_SD") (class "Default")
      (node (ref "D8") (pin "2") (pinfunction "2_2") (pintype "passive"))
      (node (ref "J4") (pin "P2") (pinfunction "CD/DAT3_P2") (pintype "bidirectional"))
      (node (ref "R10") (pin "1") (pinfunction "1_1") (pintype "passive"))
      (node (ref "U2") (pin "4") (pinfunction "IO4_4") (pintype "bidirectional"))
    )
    (net (code "50") (name "TX") (class "Default")
      (node (ref "TP1") (pin "TP") (pinfunction "TP_TP") (pintype "input"))
      (node (ref "U2") (pin "25") (pinfunction "TXD0/GPIO16_25") (pintype "bidirectional"))
    )
    (net (code "51") (name "USB_D+") (class "Default")
      (node (ref "D1") (pin "1") (pinfunction "I/O1_1_1") (pintype "bidirectional"))
      (node (ref "U2") (pin "14") (pinfunction "IO13_14") (pintype "bidirectional"))
    )
    (net (code "52") (name "USB_D-") (class "Default")
      (node (ref "D1") (pin "3") (pinfunction "I/O2_1_3") (pintype "bidirectional"))
      (node (ref "U2") (pin "13") (pinfunction "IO12_13") (pintype "bidirectional"))
    )
    (net (code "53") (name "VBAT") (class "Default")
      (node (ref "C2_BAT") (pin "1") (pinfunction "1_1") (pintype "passive"))
      (node (ref "MCP73831") (pin "3") (pinfunction "VBAT_3") (pintype "power_in"))
      (node (ref "Q1") (pin "3") (pinfunction "D_3") (pintype "bidirectional"))
      (node (ref "TP3") (pin "TP") (pinfunction "TP_TP") (pintype "input"))
      (node (ref "U4") (pin "2") (pinfunction "CELL_2") (pintype "power_in"))
      (node (ref "U4") (pin "3") (pinfunction "VDD_3") (pintype "power_in"))
    )
    (net (code "54") (name "VBUS") (class "Default")
      (node (ref "C1_BAT") (pin "1") (pinfunction "1_1") (pintype "passive"))
      (node (ref "C4_USB") (pin "1") (pinfunction "1_1") (pintype "passive"))
      (node (ref "C5_USB") (pin "1") (pinfunction "1_1") (pintype "passive"))
      (node (ref "CHG_LED") (pin "A") (pinfunction "A_A") (pintype "passive"))
      (node (ref "D1") (pin "5") (pinfunction "VBUS_5") (pintype "bidirectional"))
      (node (ref "MCP73831") (pin "4") (pinfunction "VIN_4") (pintype "power_in"))
      (node (ref "PFMF.050.1") (pin "2") (pinfunction "2_2") (pintype "passive"))
      (node (ref "TP14") (pin "TP") (pinfunction "TP_TP") (pintype "input"))
    )
    (net (code "55") (name "VRTC") (class "Default")
      (node (ref "C10_SUPERCAP") (pin "1") (pinfunction "1_1") (pintype "passive"))
      (node (ref "C8") (pin "1") (pinfunction "1_1") (pintype "passive"))
      (node (ref "R_CAPACITOR") (pin "2") (pinfunction "2_2") (pintype "passive"))
      (node (ref "U3") (pin "14") (pinfunction "VBAT_14") (pintype "power_in"))
    )
    (net (code "56") (name "VUSB") (class "Default")
      (node (ref "J2") (pin "A4") (pinfunction "A4_A4") (pintype "bidirectional"))
      (node (ref "J2") (pin "A9") (pinfunction "A9_A9") (pintype "bidirectional"))
      (node (ref "J2") (pin "B4") (pinfunction "B4_B4") (pintype "bidirectional"))
      (node (ref "J2") (pin "B9") (pinfunction "B9_B9") (pintype "bidirectional"))
      (node (ref "PFMF.050.1") (pin "1") (pinfunction "1_1") (pintype "passive"))
    )
    (net (code "57") (name "unconnected-(IC1-NC-Pad4)") (class "Default")
      (node (ref "IC1") (pin "4") (pinfunction "NC_4") (pintype "no_connect"))
    )
    (net (code "58") (name "unconnected-(IC4-NC-Pad4)") (class "Default")
      (node (ref "IC4") (pin "4") (pinfunction "NC_4") (pintype "no_connect"))
    )
    (net (code "59") (name "unconnected-(J1-Pad1)") (class "Default")
      (node (ref "J1") (pin "1") (pinfunction "1_1") (pintype "bidirectional"))
    )
    (net (code "60") (name "unconnected-(J1-Pad6)") (class "Default")
      (node (ref "J1") (pin "6") (pinfunction "6_6") (pintype "bidirectional"))
    )
    (net (code "61") (name "unconnected-(J1-Pad7)") (class "Default")
      (node (ref "J1") (pin "7") (pinfunction "7_7") (pintype "bidirectional"))
    )
    (net (code "62") (name "unconnected-(J2-PadA8)") (class "Default")
      (node (ref "J2") (pin "A8") (pinfunction "A8_A8") (pintype "bidirectional"))
    )
    (net (code "63") (name "unconnected-(J2-PadB8)") (class "Default")
      (node (ref "J2") (pin "B8") (pinfunction "B8_B8") (pintype "bidirectional"))
    )
    (net (code "64") (name "unconnected-(J4-DAT1-PadP8)") (class "Default")
      (node (ref "J4") (pin "P8") (pinfunction "DAT1_P8") (pintype "bidirectional"))
    )
    (net (code "65") (name "unconnected-(J4-DAT2-PadP1)") (class "Default")
      (node (ref "J4") (pin "P1") (pinfunction "DAT2_P1") (pintype "bidirectional"))
    )
    (net (code "66") (name "unconnected-(J4-DETECTION_1-PadS1)") (class "Default")
      (node (ref "J4") (pin "S1") (pinfunction "DETECTION_1_S1") (pintype "bidirectional"))
    )
    (net (code "67") (name "unconnected-(J4-DETECTION_2-PadS2)") (class "Default")
      (node (ref "J4") (pin "S2") (pinfunction "DETECTION_2_S2") (pintype "bidirectional"))
    )
    (net (code "68") (name "unconnected-(U2-NC-Pad22)") (class "Default")
      (node (ref "U2") (pin "22") (pinfunction "NC_22") (pintype "no_connect"))
    )
    (net (code "69") (name "unconnected-(U4-~{ALERT}-Pad5)") (class "Default")
      (node (ref "U4") (pin "5") (pinfunction "~{ALERT}_5") (pintype "output"))
    )
  )
)
